# p1_power_supply_10v.net
KiCad netlist of a schematic drawn in Altium Designer
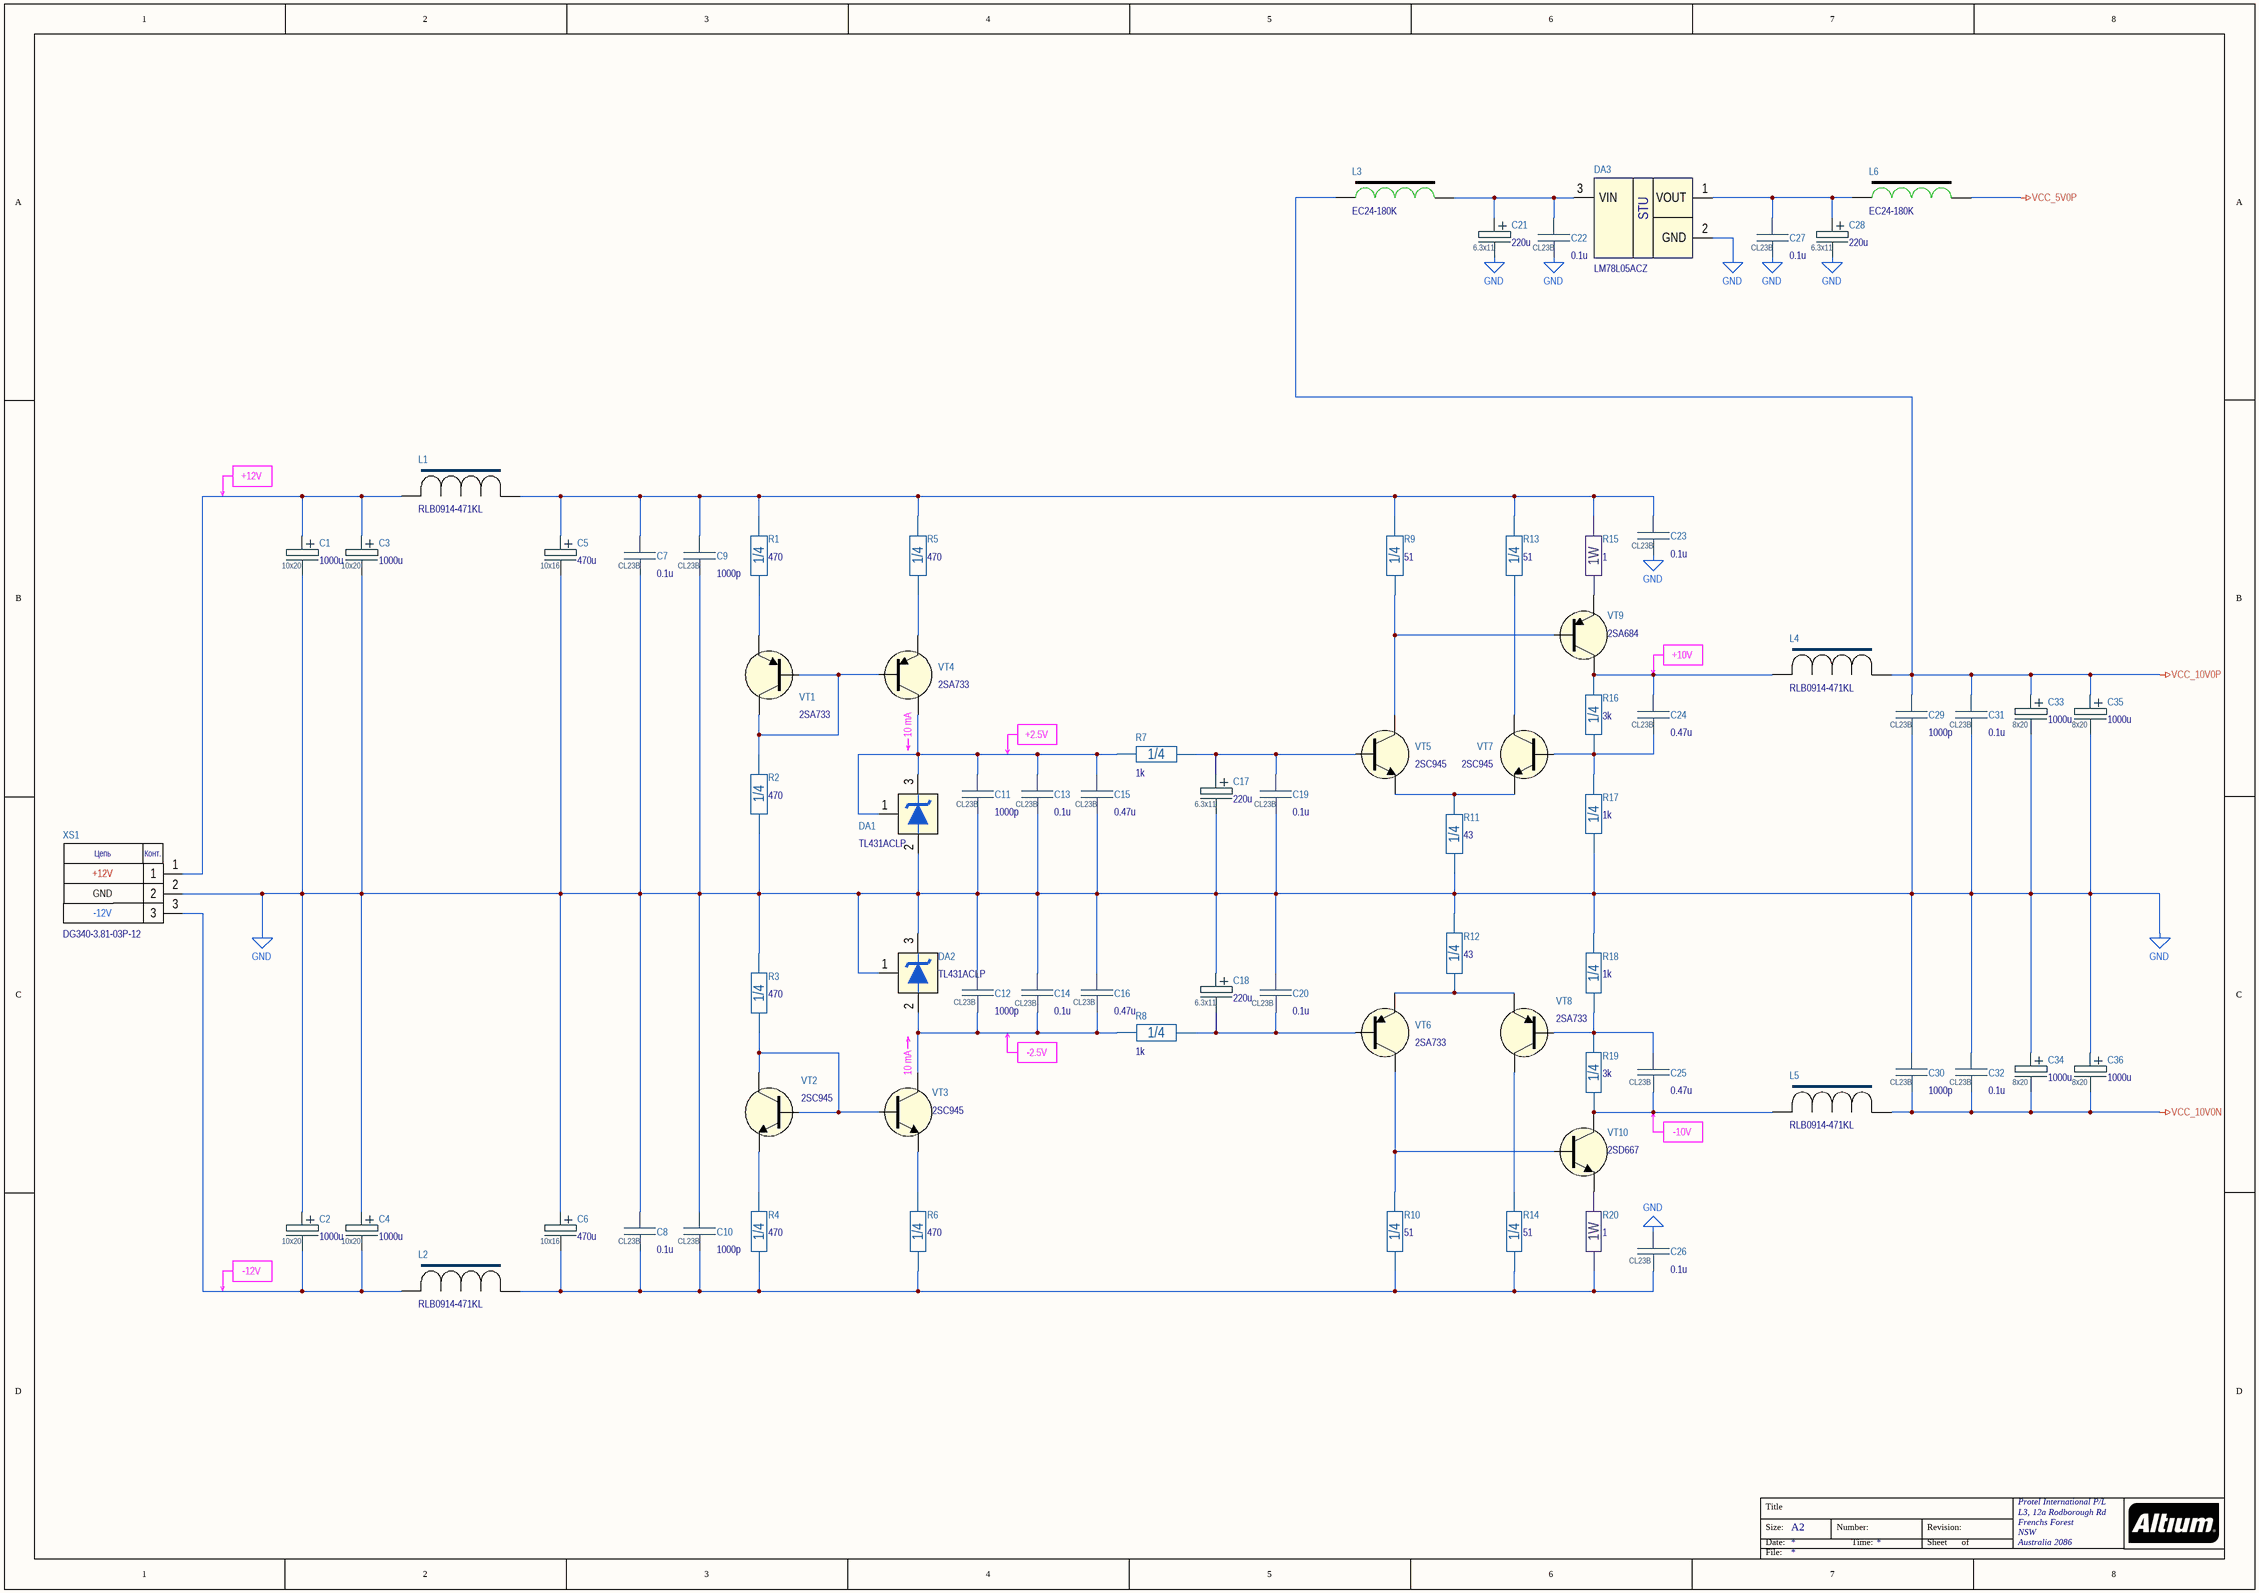
[diagram p0: p1_power_supply_10v.SchDoc]

(export (version "E")
  (design (tool "Eeschema 10.0.6"))
  (components
    (comp (ref "C1")
      (value "1000u")
      (footprint "PcbLib_RC:ECAP10X21X5_BRW")
      (description "Aluminium capacitor")
      (fields
        (field (name "TOLERANCE") "± 20 %")
        (field (name "VOLTAGE") "25V")
        (field (name "PACKAGE") "10x20")
      )
      (libsource (lib "Schlib_RC") (part "C_ECAP"))
    )
    (comp (ref "C2")
      (value "1000u")
      (footprint "PcbLib_RC:ECAP10X21X5_BRW")
      (description "Aluminium capacitor")
      (fields
        (field (name "TOLERANCE") "± 20 %")
        (field (name "VOLTAGE") "25V")
        (field (name "PACKAGE") "10x20")
      )
      (libsource (lib "Schlib_RC") (part "C_ECAP"))
    )
    (comp (ref "C3")
      (value "1000u")
      (footprint "PcbLib_RC:ECAP10X21X5_BRW")
      (description "Aluminium capacitor")
      (fields
        (field (name "TOLERANCE") "± 20 %")
        (field (name "VOLTAGE") "25V")
        (field (name "PACKAGE") "10x20")
      )
      (libsource (lib "Schlib_RC") (part "C_ECAP"))
    )
    (comp (ref "C4")
      (value "1000u")
      (footprint "PcbLib_RC:ECAP10X21X5_BRW")
      (description "Aluminium capacitor")
      (fields
        (field (name "TOLERANCE") "± 20 %")
        (field (name "VOLTAGE") "25V")
        (field (name "PACKAGE") "10x20")
      )
      (libsource (lib "Schlib_RC") (part "C_ECAP"))
    )
    (comp (ref "C5")
      (value "470u")
      (footprint "PcbLib_RC:ECAP10X17X5_BRW")
      (description "Aluminium capacitor")
      (fields
        (field (name "TOLERANCE") "± 20 %")
        (field (name "VOLTAGE") "25V")
        (field (name "PACKAGE") "10x16")
      )
      (libsource (lib "Schlib_RC") (part "C_ECAP"))
    )
    (comp (ref "C6")
      (value "470u")
      (footprint "PcbLib_RC:ECAP10X17X5_BRW")
      (description "Aluminium capacitor")
      (fields
        (field (name "TOLERANCE") "± 20 %")
        (field (name "VOLTAGE") "25V")
        (field (name "PACKAGE") "10x16")
      )
      (libsource (lib "Schlib_RC") (part "C_ECAP"))
    )
    (comp (ref "C7")
      (value "0.1u")
      (footprint "PcbLib_RC:CL23B_7.2x2.5")
      (description "Box-type metallized polyester film capacitor")
      (fields
        (field (name "TOLERANCE") "± * %")
        (field (name "VOLTAGE") "63V")
        (field (name "PACKAGE") "CL23B")
      )
      (libsource (lib "Schlib_RC") (part "CL23B"))
    )
    (comp (ref "C8")
      (value "0.1u")
      (footprint "PcbLib_RC:CL23B_7.2x2.5")
      (description "Box-type metallized polyester film capacitor")
      (fields
        (field (name "TOLERANCE") "± * %")
        (field (name "VOLTAGE") "63V")
        (field (name "PACKAGE") "CL23B")
      )
      (libsource (lib "Schlib_RC") (part "CL23B"))
    )
    (comp (ref "C9")
      (value "1000p")
      (footprint "PcbLib_RC:CL23B_7.2x2.5")
      (description "Box-type metallized polyester film capacitor")
      (fields
        (field (name "TOLERANCE") "± * %")
        (field (name "VOLTAGE") "63V")
        (field (name "PACKAGE") "CL23B")
      )
      (libsource (lib "Schlib_RC") (part "CL23B"))
    )
    (comp (ref "C10")
      (value "1000p")
      (footprint "PcbLib_RC:CL23B_7.2x2.5")
      (description "Box-type metallized polyester film capacitor")
      (fields
        (field (name "TOLERANCE") "± * %")
        (field (name "VOLTAGE") "63V")
        (field (name "PACKAGE") "CL23B")
      )
      (libsource (lib "Schlib_RC") (part "CL23B"))
    )
    (comp (ref "C11")
      (value "1000p")
      (footprint "PcbLib_RC:CL23B_7.2x2.5")
      (description "Box-type metallized polyester film capacitor")
      (fields
        (field (name "TOLERANCE") "± * %")
        (field (name "VOLTAGE") "63V")
        (field (name "PACKAGE") "CL23B")
      )
      (libsource (lib "Schlib_RC") (part "CL23B"))
    )
    (comp (ref "C12")
      (value "1000p")
      (footprint "PcbLib_RC:CL23B_7.2x2.5")
      (description "Box-type metallized polyester film capacitor")
      (fields
        (field (name "TOLERANCE") "± * %")
        (field (name "VOLTAGE") "63V")
        (field (name "PACKAGE") "CL23B")
      )
      (libsource (lib "Schlib_RC") (part "CL23B"))
    )
    (comp (ref "C13")
      (value "0.1u")
      (footprint "PcbLib_RC:CL23B_7.2x2.5")
      (description "Box-type metallized polyester film capacitor")
      (fields
        (field (name "TOLERANCE") "± * %")
        (field (name "VOLTAGE") "63V")
        (field (name "PACKAGE") "CL23B")
      )
      (libsource (lib "Schlib_RC") (part "CL23B"))
    )
    (comp (ref "C14")
      (value "0.1u")
      (footprint "PcbLib_RC:CL23B_7.2x2.5")
      (description "Box-type metallized polyester film capacitor")
      (fields
        (field (name "TOLERANCE") "± * %")
        (field (name "VOLTAGE") "63V")
        (field (name "PACKAGE") "CL23B")
      )
      (libsource (lib "Schlib_RC") (part "CL23B"))
    )
    (comp (ref "C15")
      (value "0.47u")
      (footprint "PcbLib_RC:CL23B_7.2x3.5")
      (description "Box-type metallized polyester film capacitor")
      (fields
        (field (name "TOLERANCE") "± * %")
        (field (name "VOLTAGE") "63V")
        (field (name "PACKAGE") "CL23B")
      )
      (libsource (lib "Schlib_RC") (part "CL23B"))
    )
    (comp (ref "C16")
      (value "0.47u")
      (footprint "PcbLib_RC:CL23B_7.2x3.5")
      (description "Box-type metallized polyester film capacitor")
      (fields
        (field (name "TOLERANCE") "± * %")
        (field (name "VOLTAGE") "63V")
        (field (name "PACKAGE") "CL23B")
      )
      (libsource (lib "Schlib_RC") (part "CL23B"))
    )
    (comp (ref "C17")
      (value "220u")
      (footprint "PcbLib_RC:ECAP6.3X11X2.5_BRW")
      (description "Aluminium capacitor")
      (fields
        (field (name "TOLERANCE") "± 20 %")
        (field (name "VOLTAGE") "16V")
        (field (name "PACKAGE") "6.3x11")
      )
      (libsource (lib "Schlib_RC") (part "C_ECAP"))
    )
    (comp (ref "C18")
      (value "220u")
      (footprint "PcbLib_RC:ECAP6.3X11X2.5_BRW")
      (description "Aluminium capacitor")
      (fields
        (field (name "TOLERANCE") "± 20 %")
        (field (name "VOLTAGE") "16V")
        (field (name "PACKAGE") "6.3x11")
      )
      (libsource (lib "Schlib_RC") (part "C_ECAP"))
    )
    (comp (ref "C19")
      (value "0.1u")
      (footprint "PcbLib_RC:CL23B_7.2x2.5")
      (description "Box-type metallized polyester film capacitor")
      (fields
        (field (name "TOLERANCE") "± * %")
        (field (name "VOLTAGE") "63V")
        (field (name "PACKAGE") "CL23B")
      )
      (libsource (lib "Schlib_RC") (part "CL23B"))
    )
    (comp (ref "C20")
      (value "0.1u")
      (footprint "PcbLib_RC:CL23B_7.2x2.5")
      (description "Box-type metallized polyester film capacitor")
      (fields
        (field (name "TOLERANCE") "± * %")
        (field (name "VOLTAGE") "63V")
        (field (name "PACKAGE") "CL23B")
      )
      (libsource (lib "Schlib_RC") (part "CL23B"))
    )
    (comp (ref "C21")
      (value "220u")
      (footprint "PcbLib_RC:ECAP6.3X11X2.5_BRW")
      (description "Aluminium capacitor")
      (fields
        (field (name "TOLERANCE") "± 20 %")
        (field (name "VOLTAGE") "16V")
        (field (name "PACKAGE") "6.3x11")
      )
      (libsource (lib "Schlib_RC") (part "C_ECAP"))
    )
    (comp (ref "C22")
      (value "0.1u")
      (footprint "PcbLib_RC:CL23B_7.2x2.5")
      (description "Box-type metallized polyester film capacitor")
      (fields
        (field (name "TOLERANCE") "± * %")
        (field (name "VOLTAGE") "63V")
        (field (name "PACKAGE") "CL23B")
      )
      (libsource (lib "Schlib_RC") (part "CL23B"))
    )
    (comp (ref "C23")
      (value "0.1u")
      (footprint "PcbLib_RC:CL23B_7.2x2.5")
      (description "Box-type metallized polyester film capacitor")
      (fields
        (field (name "TOLERANCE") "± * %")
        (field (name "VOLTAGE") "63V")
        (field (name "PACKAGE") "CL23B")
      )
      (libsource (lib "Schlib_RC") (part "CL23B"))
    )
    (comp (ref "C24")
      (value "0.47u")
      (footprint "PcbLib_RC:CL23B_7.2x3.5")
      (description "Box-type metallized polyester film capacitor")
      (fields
        (field (name "TOLERANCE") "± * %")
        (field (name "VOLTAGE") "63V")
        (field (name "PACKAGE") "CL23B")
      )
      (libsource (lib "Schlib_RC") (part "CL23B"))
    )
    (comp (ref "C25")
      (value "0.47u")
      (footprint "PcbLib_RC:CL23B_7.2x3.5")
      (description "Box-type metallized polyester film capacitor")
      (fields
        (field (name "TOLERANCE") "± * %")
        (field (name "VOLTAGE") "63V")
        (field (name "PACKAGE") "CL23B")
      )
      (libsource (lib "Schlib_RC") (part "CL23B"))
    )
    (comp (ref "C26")
      (value "0.1u")
      (footprint "PcbLib_RC:CL23B_7.2x2.5")
      (description "Box-type metallized polyester film capacitor")
      (fields
        (field (name "TOLERANCE") "± * %")
        (field (name "VOLTAGE") "63V")
        (field (name "PACKAGE") "CL23B")
      )
      (libsource (lib "Schlib_RC") (part "CL23B"))
    )
    (comp (ref "C27")
      (value "0.1u")
      (footprint "PcbLib_RC:CL23B_7.2x2.5")
      (description "Box-type metallized polyester film capacitor")
      (fields
        (field (name "TOLERANCE") "± * %")
        (field (name "VOLTAGE") "63V")
        (field (name "PACKAGE") "CL23B")
      )
      (libsource (lib "Schlib_RC") (part "CL23B"))
    )
    (comp (ref "C28")
      (value "220u")
      (footprint "PcbLib_RC:ECAP6.3X11X2.5_BRW")
      (description "Aluminium capacitor")
      (fields
        (field (name "TOLERANCE") "± 20 %")
        (field (name "VOLTAGE") "16V")
        (field (name "PACKAGE") "6.3x11")
      )
      (libsource (lib "Schlib_RC") (part "C_ECAP"))
    )
    (comp (ref "C29")
      (value "1000p")
      (footprint "PcbLib_RC:CL23B_7.2x2.5")
      (description "Box-type metallized polyester film capacitor")
      (fields
        (field (name "TOLERANCE") "± * %")
        (field (name "VOLTAGE") "63V")
        (field (name "PACKAGE") "CL23B")
      )
      (libsource (lib "Schlib_RC") (part "CL23B"))
    )
    (comp (ref "C30")
      (value "1000p")
      (footprint "PcbLib_RC:CL23B_7.2x2.5")
      (description "Box-type metallized polyester film capacitor")
      (fields
        (field (name "TOLERANCE") "± * %")
        (field (name "VOLTAGE") "63V")
        (field (name "PACKAGE") "CL23B")
      )
      (libsource (lib "Schlib_RC") (part "CL23B"))
    )
    (comp (ref "C31")
      (value "0.1u")
      (footprint "PcbLib_RC:CL23B_7.2x2.5")
      (description "Box-type metallized polyester film capacitor")
      (fields
        (field (name "TOLERANCE") "± * %")
        (field (name "VOLTAGE") "63V")
        (field (name "PACKAGE") "CL23B")
      )
      (libsource (lib "Schlib_RC") (part "CL23B"))
    )
    (comp (ref "C32")
      (value "0.1u")
      (footprint "PcbLib_RC:CL23B_7.2x2.5")
      (description "Box-type metallized polyester film capacitor")
      (fields
        (field (name "TOLERANCE") "± * %")
        (field (name "VOLTAGE") "63V")
        (field (name "PACKAGE") "CL23B")
      )
      (libsource (lib "Schlib_RC") (part "CL23B"))
    )
    (comp (ref "C33")
      (value "1000u")
      (footprint "PcbLib_RC:ECAP8X20X3.5_BRW")
      (description "Aluminium capacitor")
      (fields
        (field (name "TOLERANCE") "± 20 %")
        (field (name "VOLTAGE") "16V")
        (field (name "PACKAGE") "8x20")
      )
      (libsource (lib "Schlib_RC") (part "C_ECAP"))
    )
    (comp (ref "C34")
      (value "1000u")
      (footprint "PcbLib_RC:ECAP8X20X3.5_BRW")
      (description "Aluminium capacitor")
      (fields
        (field (name "TOLERANCE") "± 20 %")
        (field (name "VOLTAGE") "16V")
        (field (name "PACKAGE") "8x20")
      )
      (libsource (lib "Schlib_RC") (part "C_ECAP"))
    )
    (comp (ref "C35")
      (value "1000u")
      (footprint "PcbLib_RC:ECAP8X20X3.5_BRW")
      (description "Aluminium capacitor")
      (fields
        (field (name "TOLERANCE") "± 20 %")
        (field (name "VOLTAGE") "16V")
        (field (name "PACKAGE") "8x20")
      )
      (libsource (lib "Schlib_RC") (part "C_ECAP"))
    )
    (comp (ref "C36")
      (value "1000u")
      (footprint "PcbLib_RC:ECAP8X20X3.5_BRW")
      (description "Aluminium capacitor")
      (fields
        (field (name "TOLERANCE") "± 20 %")
        (field (name "VOLTAGE") "16V")
        (field (name "PACKAGE") "8x20")
      )
      (libsource (lib "Schlib_RC") (part "C_ECAP"))
    )
    (comp (ref "DA1")
      (value "TL431ACLP")
      (footprint "PcbLib_ICs:TO-92 (VERTICAL,LINE)")
      (description "Precision Programmable Reference")
      (fields (field (name "MANUFACTURER") "Texas Instruments"))
      (libsource (lib "Schlib_Texas_Instruments") (part "TL431ACLP"))
    )
    (comp (ref "DA2")
      (value "TL431ACLP")
      (footprint "PcbLib_ICs:TO-92 (VERTICAL,LINE)")
      (description "Precision Programmable Reference")
      (fields (field (name "MANUFACTURER") "Texas Instruments"))
      (libsource (lib "Schlib_Texas_Instruments") (part "TL431ACLP"))
    )
    (comp (ref "DA3")
      (value "LM78L05ACZ")
      (footprint "PcbLib_ICs:TO-92 (VERTICAL,LINE)")
      (description "100-mA Fixed Output Linear Regulator")
      (fields (field (name "MANUFACTURER") "Texas Instruments"))
      (libsource (lib "Schlib_Texas_Instruments") (part "LM78L05ACZ"))
    )
    (comp (ref "L1")
      (value "RLB0914-471KL")
      (footprint "PcbLib_RC:RLB0914")
      (description "Radial Inductors")
      (fields (field (name "MANUFACTURER") "Bourns Inc."))
      (libsource (lib "Schlib_Bourns") (part "RLB0914"))
    )
    (comp (ref "L2")
      (value "RLB0914-471KL")
      (footprint "PcbLib_RC:RLB0914")
      (description "Radial Inductors")
      (fields (field (name "MANUFACTURER") "Bourns Inc."))
      (libsource (lib "Schlib_Bourns") (part "RLB0914"))
    )
    (comp (ref "L3")
      (value "EC24-180K")
      (footprint "PcbLib_RC:EC24_GREEN")
      (description "Axial leaded coated inductors")
      (fields (field (name "MANUFACTURER") "3L Electronic"))
      (libsource (lib "Schlib_RC") (part "EC24"))
    )
    (comp (ref "L4")
      (value "RLB0914-471KL")
      (footprint "PcbLib_RC:RLB0914")
      (description "Radial Inductors")
      (fields (field (name "MANUFACTURER") "Bourns Inc."))
      (libsource (lib "Schlib_Bourns") (part "RLB0914"))
    )
    (comp (ref "L5")
      (value "RLB0914-471KL")
      (footprint "PcbLib_RC:RLB0914")
      (description "Radial Inductors")
      (fields (field (name "MANUFACTURER") "Bourns Inc."))
      (libsource (lib "Schlib_Bourns") (part "RLB0914"))
    )
    (comp (ref "L6")
      (value "EC24-180K")
      (footprint "PcbLib_RC:EC24_GREEN")
      (description "Axial leaded coated inductors")
      (fields (field (name "MANUFACTURER") "3L Electronic"))
      (libsource (lib "Schlib_RC") (part "EC24"))
    )
    (comp (ref "R1")
      (value "470")
      (footprint "PcbLib_RC:CFR-25")
      (description "Resistor 1/4W")
      (fields
        (field (name "TOLERANCE") "± 0.1 %")
        (field (name "PART NUMBER") "MFP-25BRD52-470R")
        (field (name "PACKAGE") "1/4")
      )
      (libsource (lib "Schlib_RC") (part "CF25"))
    )
    (comp (ref "R2")
      (value "470")
      (footprint "PcbLib_RC:CFR-25")
      (description "Resistor 1/4W")
      (fields
        (field (name "TOLERANCE") "± 0.1 %")
        (field (name "PART NUMBER") "MFP-25BRD52-470R")
        (field (name "PACKAGE") "1/4")
      )
      (libsource (lib "Schlib_RC") (part "CF25"))
    )
    (comp (ref "R3")
      (value "470")
      (footprint "PcbLib_RC:CFR-25")
      (description "Resistor 1/4W")
      (fields
        (field (name "TOLERANCE") "± 0.1 %")
        (field (name "PART NUMBER") "MFP-25BRD52-470R")
        (field (name "PACKAGE") "1/4")
      )
      (libsource (lib "Schlib_RC") (part "CF25"))
    )
    (comp (ref "R4")
      (value "470")
      (footprint "PcbLib_RC:CFR-25")
      (description "Resistor 1/4W")
      (fields
        (field (name "TOLERANCE") "± 0.1 %")
        (field (name "PART NUMBER") "MFP-25BRD52-470R")
        (field (name "PACKAGE") "1/4")
      )
      (libsource (lib "Schlib_RC") (part "CF25"))
    )
    (comp (ref "R5")
      (value "470")
      (footprint "PcbLib_RC:CFR-25")
      (description "Resistor 1/4W")
      (fields
        (field (name "TOLERANCE") "± 0.1 %")
        (field (name "PART NUMBER") "MFP-25BRD52-470R")
        (field (name "PACKAGE") "1/4")
      )
      (libsource (lib "Schlib_RC") (part "CF25"))
    )
    (comp (ref "R6")
      (value "470")
      (footprint "PcbLib_RC:CFR-25")
      (description "Resistor 1/4W")
      (fields
        (field (name "TOLERANCE") "± 0.1 %")
        (field (name "PART NUMBER") "MFP-25BRD52-470R")
        (field (name "PACKAGE") "1/4")
      )
      (libsource (lib "Schlib_RC") (part "CF25"))
    )
    (comp (ref "R7")
      (value "1k")
      (footprint "PcbLib_RC:CFR-25")
      (description "Resistor 1/4W")
      (fields
        (field (name "TOLERANCE") "± 1 %")
        (field (name "PART NUMBER") "MFR-25FTF52-10K")
        (field (name "PACKAGE") "1/4")
      )
      (libsource (lib "Schlib_RC") (part "CF25"))
    )
    (comp (ref "R8")
      (value "1k")
      (footprint "PcbLib_RC:CFR-25")
      (description "Resistor 1/4W")
      (fields
        (field (name "TOLERANCE") "± 1 %")
        (field (name "PART NUMBER") "MFR-25FTF52-10K")
        (field (name "PACKAGE") "1/4")
      )
      (libsource (lib "Schlib_RC") (part "CF25"))
    )
    (comp (ref "R9")
      (value "51")
      (footprint "PcbLib_RC:CFR-25")
      (description "Resistor 1/4W")
      (fields
        (field (name "TOLERANCE") "± 0.1 %")
        (field (name "PART NUMBER") "MFP-25BRD52-51R")
        (field (name "PACKAGE") "1/4")
      )
      (libsource (lib "Schlib_RC") (part "CF25"))
    )
    (comp (ref "R10")
      (value "51")
      (footprint "PcbLib_RC:CFR-25")
      (description "Resistor 1/4W")
      (fields
        (field (name "TOLERANCE") "± 0.1 %")
        (field (name "PART NUMBER") "MFP-25BRD52-51R")
        (field (name "PACKAGE") "1/4")
      )
      (libsource (lib "Schlib_RC") (part "CF25"))
    )
    (comp (ref "R11")
      (value "43")
      (footprint "PcbLib_RC:CFR-25")
      (description "Resistor 1/4W")
      (fields
        (field (name "TOLERANCE") "± 1 %")
        (field (name "PART NUMBER") "MFR-25FTF52-43R")
        (field (name "PACKAGE") "1/4")
      )
      (libsource (lib "Schlib_RC") (part "CF25"))
    )
    (comp (ref "R12")
      (value "43")
      (footprint "PcbLib_RC:CFR-25")
      (description "Resistor 1/4W")
      (fields
        (field (name "TOLERANCE") "± 1 %")
        (field (name "PART NUMBER") "MFR-25FTF52-43R")
        (field (name "PACKAGE") "1/4")
      )
      (libsource (lib "Schlib_RC") (part "CF25"))
    )
    (comp (ref "R13")
      (value "51")
      (footprint "PcbLib_RC:CFR-25")
      (description "Resistor 1/4W")
      (fields
        (field (name "TOLERANCE") "± 0.1 %")
        (field (name "PART NUMBER") "MFP-25BRD52-51R")
        (field (name "PACKAGE") "1/4")
      )
      (libsource (lib "Schlib_RC") (part "CF25"))
    )
    (comp (ref "R14")
      (value "51")
      (footprint "PcbLib_RC:CFR-25")
      (description "Resistor 1/4W")
      (fields
        (field (name "TOLERANCE") "± 0.1 %")
        (field (name "PART NUMBER") "MFP-25BRD52-51R")
        (field (name "PACKAGE") "1/4")
      )
      (libsource (lib "Schlib_RC") (part "CF25"))
    )
    (comp (ref "R15")
      (value "1")
      (footprint "PcbLib_RC:CFR-100")
      (description "Resistor 1W")
      (fields
        (field (name "TOLERANCE") "± 1 %")
        (field (name "PART NUMBER") "KNP100FB-73-1R")
        (field (name "PACKAGE") "1W")
      )
      (libsource (lib "Schlib_RC") (part "CF100"))
    )
    (comp (ref "R16")
      (value "3k")
      (footprint "PcbLib_RC:CFR-25")
      (description "Resistor 1/4W")
      (fields
        (field (name "TOLERANCE") "± 1 %")
        (field (name "PART NUMBER") "MFR-25FTF52-3K")
        (field (name "PACKAGE") "1/4")
      )
      (libsource (lib "Schlib_RC") (part "CF25"))
    )
    (comp (ref "R17")
      (value "1k")
      (footprint "PcbLib_RC:CFR-25")
      (description "Resistor 1/4W")
      (fields
        (field (name "TOLERANCE") "± 1 %")
        (field (name "PART NUMBER") "MFR-25FTF52-10K")
        (field (name "PACKAGE") "1/4")
      )
      (libsource (lib "Schlib_RC") (part "CF25"))
    )
    (comp (ref "R18")
      (value "1k")
      (footprint "PcbLib_RC:CFR-25")
      (description "Resistor 1/4W")
      (fields
        (field (name "TOLERANCE") "± 1 %")
        (field (name "PART NUMBER") "MFR-25FTF52-10K")
        (field (name "PACKAGE") "1/4")
      )
      (libsource (lib "Schlib_RC") (part "CF25"))
    )
    (comp (ref "R19")
      (value "3k")
      (footprint "PcbLib_RC:CFR-25")
      (description "Resistor 1/4W")
      (fields
        (field (name "TOLERANCE") "± 1 %")
        (field (name "PART NUMBER") "MFR-25FTF52-3K")
        (field (name "PACKAGE") "1/4")
      )
      (libsource (lib "Schlib_RC") (part "CF25"))
    )
    (comp (ref "R20")
      (value "1")
      (footprint "PcbLib_RC:CFR-100")
      (description "Resistor 1W")
      (fields
        (field (name "TOLERANCE") "± 1 %")
        (field (name "PART NUMBER") "KNP100FB-73-1R")
        (field (name "PACKAGE") "1W")
      )
      (libsource (lib "Schlib_RC") (part "CF100"))
    )
    (comp (ref "VT1")
      (value "2SA733")
      (footprint "PcbLib_ICs:TO-92 (VERTICAL,LINE)")
      (description "General Purpose p-n-p Transistors")
      (fields (field (name "MANUFACTURER") "NEC"))
      (libsource (lib "Schlib_NEC") (part "2SA733"))
    )
    (comp (ref "VT2")
      (value "2SC945")
      (footprint "PcbLib_ICs:TO-92 (VERTICAL,LINE)")
      (description "General Purpose n-p-n Transistors")
      (fields (field (name "MANUFACTURER") "NEC"))
      (libsource (lib "Schlib_NEC") (part "2SC945"))
    )
    (comp (ref "VT3")
      (value "2SC945")
      (footprint "PcbLib_ICs:TO-92 (VERTICAL,LINE)")
      (description "General Purpose n-p-n Transistors")
      (fields (field (name "MANUFACTURER") "NEC"))
      (libsource (lib "Schlib_NEC") (part "2SC945"))
    )
    (comp (ref "VT4")
      (value "2SA733")
      (footprint "PcbLib_ICs:TO-92 (VERTICAL,LINE)")
      (description "General Purpose p-n-p Transistors")
      (fields (field (name "MANUFACTURER") "NEC"))
      (libsource (lib "Schlib_NEC") (part "2SA733"))
    )
    (comp (ref "VT5")
      (value "2SC945")
      (footprint "PcbLib_ICs:TO-92 (VERTICAL,LINE)")
      (description "General Purpose n-p-n Transistors")
      (fields (field (name "MANUFACTURER") "NEC"))
      (libsource (lib "Schlib_NEC") (part "2SC945"))
    )
    (comp (ref "VT6")
      (value "2SA733")
      (footprint "PcbLib_ICs:TO-92 (VERTICAL,LINE)")
      (description "General Purpose p-n-p Transistors")
      (fields (field (name "MANUFACTURER") "NEC"))
      (libsource (lib "Schlib_NEC") (part "2SA733"))
    )
    (comp (ref "VT7")
      (value "2SC945")
      (footprint "PcbLib_ICs:TO-92 (VERTICAL,LINE)")
      (description "General Purpose n-p-n Transistors")
      (fields (field (name "MANUFACTURER") "NEC"))
      (libsource (lib "Schlib_NEC") (part "2SC945"))
    )
    (comp (ref "VT8")
      (value "2SA733")
      (footprint "PcbLib_ICs:TO-92 (VERTICAL,LINE)")
      (description "General Purpose p-n-p Transistors")
      (fields (field (name "MANUFACTURER") "NEC"))
      (libsource (lib "Schlib_NEC") (part "2SA733"))
    )
    (comp (ref "VT9")
      (value "2SA684")
      (footprint "PcbLib_ICs:TO-92L (VERTICAL,LINE)")
      (description "General Purpose p-n-p Transistors -60V, -1A")
      (fields (field (name "MANUFACTURER") "Secos"))
      (libsource (lib "Schlib_OtherComponents") (part "2SA684"))
    )
    (comp (ref "VT10")
      (value "2SD667")
      (footprint "PcbLib_ICs:TO-92L (VERTICAL,LINE)")
      (description "General Purpose n-p-n Transistors 120V, 1A")
      (fields (field (name "MANUFACTURER") "Secos"))
      (libsource (lib "Schlib_OtherComponents") (part "2SD667"))
    )
    (comp (ref "XS1")
      (value "DG340-3.81-03P-12")
      (footprint "PcbLib_Connectors:DG340-3.81-03P")
      (description "3-way screw terminal, pitch 150mils (3.81mm)")
      (fields (field (name "MANUFACTURER") "DEGSON"))
      (libsource (lib "Schlib_OtherComponents") (part "DG340-3.81-03P-12"))
    )
  )
  (nets
    (net (code "1") (name "GND") (class "Default")
      (node (ref "C1") (pin "2") (pinfunction "2_2") (pintype "passive"))
      (node (ref "C10") (pin "1") (pinfunction "1_1") (pintype "passive"))
      (node (ref "C11") (pin "2") (pinfunction "2_2") (pintype "passive"))
      (node (ref "C12") (pin "2") (pinfunction "2_2") (pintype "passive"))
      (node (ref "C13") (pin "2") (pinfunction "2_2") (pintype "passive"))
      (node (ref "C14") (pin "2") (pinfunction "2_2") (pintype "passive"))
      (node (ref "C15") (pin "2") (pinfunction "2_2") (pintype "passive"))
      (node (ref "C16") (pin "2") (pinfunction "2_2") (pintype "passive"))
      (node (ref "C17") (pin "2") (pinfunction "2_2") (pintype "passive"))
      (node (ref "C18") (pin "1") (pinfunction "1_1") (pintype "passive"))
      (node (ref "C19") (pin "2") (pinfunction "2_2") (pintype "passive"))
      (node (ref "C2") (pin "1") (pinfunction "1_1") (pintype "passive"))
      (node (ref "C20") (pin "2") (pinfunction "2_2") (pintype "passive"))
      (node (ref "C21") (pin "2") (pinfunction "2_2") (pintype "passive"))
      (node (ref "C22") (pin "2") (pinfunction "2_2") (pintype "passive"))
      (node (ref "C23") (pin "2") (pinfunction "2_2") (pintype "passive"))
      (node (ref "C26") (pin "2") (pinfunction "2_2") (pintype "passive"))
      (node (ref "C27") (pin "2") (pinfunction "2_2") (pintype "passive"))
      (node (ref "C28") (pin "2") (pinfunction "2_2") (pintype "passive"))
      (node (ref "C29") (pin "2") (pinfunction "2_2") (pintype "passive"))
      (node (ref "C3") (pin "2") (pinfunction "2_2") (pintype "passive"))
      (node (ref "C30") (pin "1") (pinfunction "1_1") (pintype "passive"))
      (node (ref "C31") (pin "2") (pinfunction "2_2") (pintype "passive"))
      (node (ref "C32") (pin "1") (pinfunction "1_1") (pintype "passive"))
      (node (ref "C33") (pin "2") (pinfunction "2_2") (pintype "passive"))
      (node (ref "C34") (pin "1") (pinfunction "1_1") (pintype "passive"))
      (node (ref "C35") (pin "2") (pinfunction "2_2") (pintype "passive"))
      (node (ref "C36") (pin "1") (pinfunction "1_1") (pintype "passive"))
      (node (ref "C4") (pin "1") (pinfunction "1_1") (pintype "passive"))
      (node (ref "C5") (pin "2") (pinfunction "2_2") (pintype "passive"))
      (node (ref "C6") (pin "1") (pinfunction "1_1") (pintype "passive"))
      (node (ref "C7") (pin "2") (pinfunction "2_2") (pintype "passive"))
      (node (ref "C8") (pin "1") (pinfunction "1_1") (pintype "passive"))
      (node (ref "C9") (pin "2") (pinfunction "2_2") (pintype "passive"))
      (node (ref "DA1") (pin "2") (pinfunction "ANODE_2") (pintype "passive"))
      (node (ref "DA2") (pin "1") (pinfunction "REF_1") (pintype "passive"))
      (node (ref "DA2") (pin "3") (pinfunction "CATHODE_3") (pintype "passive"))
      (node (ref "DA3") (pin "2") (pinfunction "GND_2") (pintype "power_in"))
      (node (ref "R11") (pin "2") (pinfunction "2_2") (pintype "passive"))
      (node (ref "R12") (pin "2") (pinfunction "2_2") (pintype "passive"))
      (node (ref "R17") (pin "2") (pinfunction "2_2") (pintype "passive"))
      (node (ref "R18") (pin "2") (pinfunction "2_2") (pintype "passive"))
      (node (ref "R2") (pin "1") (pinfunction "1_1") (pintype "passive"))
      (node (ref "R3") (pin "1") (pinfunction "1_1") (pintype "passive"))
      (node (ref "XS1") (pin "2") (pinfunction "2_2") (pintype "passive"))
    )
    (net (code "2") (name "Net-(C1-Pad1)") (class "Default")
      (node (ref "C1") (pin "1") (pinfunction "1_1") (pintype "passive"))
      (node (ref "C3") (pin "1") (pinfunction "1_1") (pintype "passive"))
      (node (ref "L1") (pin "1") (pinfunction "1_1") (pintype "passive"))
      (node (ref "XS1") (pin "1") (pinfunction "1_1") (pintype "passive"))
    )
    (net (code "3") (name "Net-(C2-Pad2)") (class "Default")
      (node (ref "C2") (pin "2") (pinfunction "2_2") (pintype "passive"))
      (node (ref "C4") (pin "2") (pinfunction "2_2") (pintype "passive"))
      (node (ref "L2") (pin "1") (pinfunction "1_1") (pintype "passive"))
      (node (ref "XS1") (pin "3") (pinfunction "3_3") (pintype "passive"))
    )
    (net (code "4") (name "Net-(C10-Pad2)") (class "Default")
      (node (ref "C10") (pin "2") (pinfunction "2_2") (pintype "passive"))
      (node (ref "C26") (pin "1") (pinfunction "1_1") (pintype "passive"))
      (node (ref "C6") (pin "2") (pinfunction "2_2") (pintype "passive"))
      (node (ref "C8") (pin "2") (pinfunction "2_2") (pintype "passive"))
      (node (ref "L2") (pin "2") (pinfunction "2_2") (pintype "passive"))
      (node (ref "R10") (pin "2") (pinfunction "2_2") (pintype "passive"))
      (node (ref "R14") (pin "2") (pinfunction "2_2") (pintype "passive"))
      (node (ref "R20") (pin "2") (pinfunction "2_2") (pintype "passive"))
      (node (ref "R4") (pin "2") (pinfunction "2_2") (pintype "passive"))
      (node (ref "R6") (pin "2") (pinfunction "2_2") (pintype "passive"))
    )
    (net (code "5") (name "Net-(C23-Pad1)") (class "Default")
      (node (ref "C23") (pin "1") (pinfunction "1_1") (pintype "passive"))
      (node (ref "C5") (pin "1") (pinfunction "1_1") (pintype "passive"))
      (node (ref "C7") (pin "1") (pinfunction "1_1") (pintype "passive"))
      (node (ref "C9") (pin "1") (pinfunction "1_1") (pintype "passive"))
      (node (ref "L1") (pin "2") (pinfunction "2_2") (pintype "passive"))
      (node (ref "R1") (pin "2") (pinfunction "2_2") (pintype "passive"))
      (node (ref "R13") (pin "2") (pinfunction "2_2") (pintype "passive"))
      (node (ref "R15") (pin "2") (pinfunction "2_2") (pintype "passive"))
      (node (ref "R5") (pin "2") (pinfunction "2_2") (pintype "passive"))
      (node (ref "R9") (pin "2") (pinfunction "2_2") (pintype "passive"))
    )
    (net (code "6") (name "Net-(DA1-CATHODE)") (class "Default")
      (node (ref "C11") (pin "1") (pinfunction "1_1") (pintype "passive"))
      (node (ref "C13") (pin "1") (pinfunction "1_1") (pintype "passive"))
      (node (ref "C15") (pin "1") (pinfunction "1_1") (pintype "passive"))
      (node (ref "DA1") (pin "1") (pinfunction "REF_1") (pintype "passive"))
      (node (ref "DA1") (pin "3") (pinfunction "CATHODE_3") (pintype "passive"))
      (node (ref "R7") (pin "2") (pinfunction "2_2") (pintype "passive"))
      (node (ref "VT4") (pin "2") (pinfunction "C_2") (pintype "passive"))
    )
    (net (code "7") (name "Net-(DA2-ANODE)") (class "Default")
      (node (ref "C12") (pin "1") (pinfunction "1_1") (pintype "passive"))
      (node (ref "C14") (pin "1") (pinfunction "1_1") (pintype "passive"))
      (node (ref "C16") (pin "1") (pinfunction "1_1") (pintype "passive"))
      (node (ref "DA2") (pin "2") (pinfunction "ANODE_2") (pintype "passive"))
      (node (ref "R8") (pin "2") (pinfunction "2_2") (pintype "passive"))
      (node (ref "VT3") (pin "2") (pinfunction "C_2") (pintype "passive"))
    )
    (net (code "8") (name "Net-(DA3-VIN)") (class "Default")
      (node (ref "C21") (pin "1") (pinfunction "1_1") (pintype "passive"))
      (node (ref "C22") (pin "1") (pinfunction "1_1") (pintype "passive"))
      (node (ref "DA3") (pin "3") (pinfunction "VIN_3") (pintype "power_in"))
      (node (ref "L3") (pin "2") (pinfunction "2_2") (pintype "passive"))
    )
    (net (code "9") (name "Net-(DA3-VOUT)") (class "Default")
      (node (ref "C27") (pin "1") (pinfunction "1_1") (pintype "passive"))
      (node (ref "C28") (pin "1") (pinfunction "1_1") (pintype "passive"))
      (node (ref "DA3") (pin "1") (pinfunction "VOUT_1") (pintype "power_in"))
      (node (ref "L6") (pin "1") (pinfunction "1_1") (pintype "passive"))
    )
    (net (code "10") (name "Net-(VT1-B)") (class "Default")
      (node (ref "R2") (pin "2") (pinfunction "2_2") (pintype "passive"))
      (node (ref "VT1") (pin "1") (pinfunction "B_1") (pintype "passive"))
      (node (ref "VT1") (pin "2") (pinfunction "C_2") (pintype "passive"))
      (node (ref "VT4") (pin "1") (pinfunction "B_1") (pintype "passive"))
    )
    (net (code "11") (name "Net-(VT1-E)") (class "Default")
      (node (ref "R1") (pin "1") (pinfunction "1_1") (pintype "passive"))
      (node (ref "VT1") (pin "3") (pinfunction "E_3") (pintype "passive"))
    )
    (net (code "12") (name "Net-(VT2-B)") (class "Default")
      (node (ref "R3") (pin "2") (pinfunction "2_2") (pintype "passive"))
      (node (ref "VT2") (pin "1") (pinfunction "B_1") (pintype "passive"))
      (node (ref "VT2") (pin "2") (pinfunction "C_2") (pintype "passive"))
      (node (ref "VT3") (pin "1") (pinfunction "B_1") (pintype "passive"))
    )
    (net (code "13") (name "Net-(VT2-E)") (class "Default")
      (node (ref "R4") (pin "1") (pinfunction "1_1") (pintype "passive"))
      (node (ref "VT2") (pin "3") (pinfunction "E_3") (pintype "passive"))
    )
    (net (code "14") (name "Net-(VT3-E)") (class "Default")
      (node (ref "R6") (pin "1") (pinfunction "1_1") (pintype "passive"))
      (node (ref "VT3") (pin "3") (pinfunction "E_3") (pintype "passive"))
    )
    (net (code "15") (name "Net-(VT4-E)") (class "Default")
      (node (ref "R5") (pin "1") (pinfunction "1_1") (pintype "passive"))
      (node (ref "VT4") (pin "3") (pinfunction "E_3") (pintype "passive"))
    )
    (net (code "16") (name "Net-(VT5-B)") (class "Default")
      (node (ref "C17") (pin "1") (pinfunction "1_1") (pintype "passive"))
      (node (ref "C19") (pin "1") (pinfunction "1_1") (pintype "passive"))
      (node (ref "R7") (pin "1") (pinfunction "1_1") (pintype "passive"))
      (node (ref "VT5") (pin "1") (pinfunction "B_1") (pintype "passive"))
    )
    (net (code "17") (name "Net-(VT5-C)") (class "Default")
      (node (ref "R9") (pin "1") (pinfunction "1_1") (pintype "passive"))
      (node (ref "VT5") (pin "2") (pinfunction "C_2") (pintype "passive"))
      (node (ref "VT9") (pin "3") (pinfunction "B_3") (pintype "passive"))
    )
    (net (code "18") (name "Net-(VT5-E)") (class "Default")
      (node (ref "R11") (pin "1") (pinfunction "1_1") (pintype "passive"))
      (node (ref "VT5") (pin "3") (pinfunction "E_3") (pintype "passive"))
      (node (ref "VT7") (pin "3") (pinfunction "E_3") (pintype "passive"))
    )
    (net (code "19") (name "Net-(VT6-B)") (class "Default")
      (node (ref "C18") (pin "2") (pinfunction "2_2") (pintype "passive"))
      (node (ref "C20") (pin "1") (pinfunction "1_1") (pintype "passive"))
      (node (ref "R8") (pin "1") (pinfunction "1_1") (pintype "passive"))
      (node (ref "VT6") (pin "1") (pinfunction "B_1") (pintype "passive"))
    )
    (net (code "20") (name "Net-(VT6-E)") (class "Default")
      (node (ref "R12") (pin "1") (pinfunction "1_1") (pintype "passive"))
      (node (ref "VT6") (pin "3") (pinfunction "E_3") (pintype "passive"))
      (node (ref "VT8") (pin "3") (pinfunction "E_3") (pintype "passive"))
    )
    (net (code "21") (name "Net-(VT7-B)") (class "Default")
      (node (ref "C24") (pin "2") (pinfunction "2_2") (pintype "passive"))
      (node (ref "R16") (pin "2") (pinfunction "2_2") (pintype "passive"))
      (node (ref "R17") (pin "1") (pinfunction "1_1") (pintype "passive"))
      (node (ref "VT7") (pin "1") (pinfunction "B_1") (pintype "passive"))
    )
    (net (code "22") (name "Net-(VT7-C)") (class "Default")
      (node (ref "R13") (pin "1") (pinfunction "1_1") (pintype "passive"))
      (node (ref "VT7") (pin "2") (pinfunction "C_2") (pintype "passive"))
    )
    (net (code "23") (name "Net-(VT8-B)") (class "Default")
      (node (ref "C25") (pin "2") (pinfunction "2_2") (pintype "passive"))
      (node (ref "R18") (pin "1") (pinfunction "1_1") (pintype "passive"))
      (node (ref "R19") (pin "2") (pinfunction "2_2") (pintype "passive"))
      (node (ref "VT8") (pin "1") (pinfunction "B_1") (pintype "passive"))
    )
    (net (code "24") (name "Net-(VT8-C)") (class "Default")
      (node (ref "R14") (pin "1") (pinfunction "1_1") (pintype "passive"))
      (node (ref "VT8") (pin "2") (pinfunction "C_2") (pintype "passive"))
    )
    (net (code "25") (name "Net-(VT9-C)") (class "Default")
      (node (ref "C24") (pin "1") (pinfunction "1_1") (pintype "passive"))
      (node (ref "L4") (pin "1") (pinfunction "1_1") (pintype "passive"))
      (node (ref "R16") (pin "1") (pinfunction "1_1") (pintype "passive"))
      (node (ref "VT9") (pin "2") (pinfunction "C_2") (pintype "passive"))
    )
    (net (code "26") (name "Net-(VT9-E)") (class "Default")
      (node (ref "R15") (pin "1") (pinfunction "1_1") (pintype "passive"))
      (node (ref "VT9") (pin "1") (pinfunction "E_1") (pintype "passive"))
    )
    (net (code "27") (name "Net-(VT10-B)") (class "Default")
      (node (ref "R10") (pin "1") (pinfunction "1_1") (pintype "passive"))
      (node (ref "VT10") (pin "3") (pinfunction "B_3") (pintype "passive"))
      (node (ref "VT6") (pin "2") (pinfunction "C_2") (pintype "passive"))
    )
    (net (code "28") (name "Net-(VT10-C)") (class "Default")
      (node (ref "C25") (pin "1") (pinfunction "1_1") (pintype "passive"))
      (node (ref "L5") (pin "1") (pinfunction "1_1") (pintype "passive"))
      (node (ref "R19") (pin "1") (pinfunction "1_1") (pintype "passive"))
      (node (ref "VT10") (pin "2") (pinfunction "C_2") (pintype "passive"))
    )
    (net (code "29") (name "Net-(VT10-E)") (class "Default")
      (node (ref "R20") (pin "1") (pinfunction "1_1") (pintype "passive"))
      (node (ref "VT10") (pin "1") (pinfunction "E_1") (pintype "passive"))
    )
    (net (code "30") (name "VCC_5V0P") (class "Default")
      (node (ref "L6") (pin "2") (pinfunction "2_2") (pintype "passive"))
    )
    (net (code "31") (name "VCC_10V0N") (class "Default")
      (node (ref "C30") (pin "2") (pinfunction "2_2") (pintype "passive"))
      (node (ref "C32") (pin "2") (pinfunction "2_2") (pintype "passive"))
      (node (ref "C34") (pin "2") (pinfunction "2_2") (pintype "passive"))
      (node (ref "C36") (pin "2") (pinfunction "2_2") (pintype "passive"))
      (node (ref "L5") (pin "2") (pinfunction "2_2") (pintype "passive"))
    )
    (net (code "32") (name "VCC_10V0P") (class "Default")
      (node (ref "C29") (pin "1") (pinfunction "1_1") (pintype "passive"))
      (node (ref "C31") (pin "1") (pinfunction "1_1") (pintype "passive"))
      (node (ref "C33") (pin "1") (pinfunction "1_1") (pintype "passive"))
      (node (ref "C35") (pin "1") (pinfunction "1_1") (pintype "passive"))
      (node (ref "L3") (pin "1") (pinfunction "1_1") (pintype "passive"))
      (node (ref "L4") (pin "2") (pinfunction "2_2") (pintype "passive"))
    )
  )
)
